# SENS.net
KiCad netlist of a schematic drawn in Altium Designer
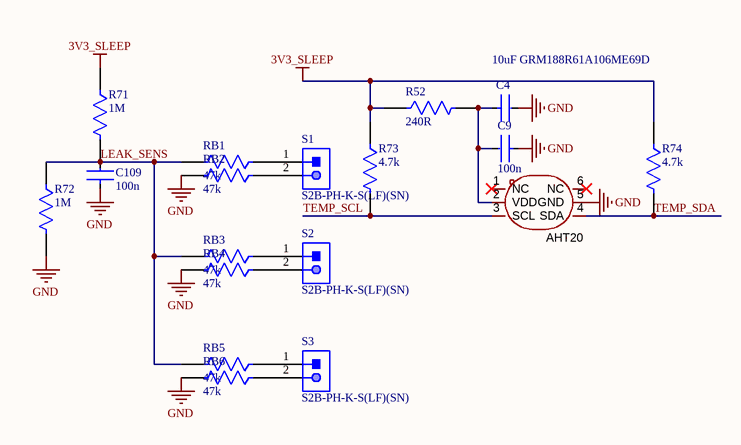
[diagram p0: SENS.SchDoc]

(export (version "E")
  (design (tool "Eeschema 10.0.6"))
  (components
    (comp (ref "C4")
      (value "10uF GRM188R61A106ME69D")
      (footprint "FP-GRM188-0_15-MFG")
      (description "C19702")
      (fields (field (name "TOLERANCE") "20%"))
      (libsource (lib "LEAKCAM") (part "CMP-06035-003612-1"))
    )
    (comp (ref "C9")
      (value "100n")
      (footprint "CAP_0402")
      (description "C307331")
      (fields (field (name "TOLERANCE") "10%"))
      (libsource (lib "LEAKCAM") (part "CMP-03422-001116-1"))
    )
    (comp (ref "C109")
      (value "100n")
      (footprint "CAP_0402")
      (description "C307331")
      (fields (field (name "TOLERANCE") "10%"))
      (libsource (lib "LEAKCAM") (part "CMP-03422-001116-1"))
    )
    (comp (ref "R52")
      (value "240R")
      (footprint "RES_0402")
      (description "C324768")
      (fields (field (name "TOLERANCE") "1%"))
      (libsource (lib "LEAKCAM") (part "CMP-03412-016018-1"))
    )
    (comp (ref "R71")
      (value "1M")
      (footprint "RES_0402")
      (description "C26083")
      (fields (field (name "TOLERANCE") "1%"))
      (libsource (lib "LEAKCAM") (part "CMP-03412-016018-1"))
    )
    (comp (ref "R72")
      (value "1M")
      (footprint "RES_0402")
      (description "C26083")
      (fields (field (name "TOLERANCE") "1%"))
      (libsource (lib "LEAKCAM") (part "CMP-03412-016018-1"))
    )
    (comp (ref "R73")
      (value "4.7k")
      (footprint "RES_0402")
      (description "C25900")
      (fields (field (name "TOLERANCE") "1%"))
      (libsource (lib "LEAKCAM") (part "CMP-03412-016018-1"))
    )
    (comp (ref "R74")
      (value "4.7k")
      (footprint "RES_0402")
      (description "C25900")
      (fields (field (name "TOLERANCE") "1%"))
      (libsource (lib "LEAKCAM") (part "CMP-03412-016018-1"))
    )
    (comp (ref "RB1")
      (value "47k")
      (footprint "RES_0402")
      (description "C25792")
      (fields (field (name "TOLERANCE") "1%"))
      (libsource (lib "LEAKCAM") (part "CMP-03412-016018-1"))
    )
    (comp (ref "RB2")
      (value "47k")
      (footprint "RES_0402")
      (description "C25792")
      (fields (field (name "TOLERANCE") "1%"))
      (libsource (lib "LEAKCAM") (part "CMP-03412-016018-1"))
    )
    (comp (ref "RB3")
      (value "47k")
      (footprint "RES_0402")
      (description "C25792")
      (fields (field (name "TOLERANCE") "1%"))
      (libsource (lib "LEAKCAM") (part "CMP-03412-016018-1"))
    )
    (comp (ref "RB4")
      (value "47k")
      (footprint "RES_0402")
      (description "C25792")
      (fields (field (name "TOLERANCE") "1%"))
      (libsource (lib "LEAKCAM") (part "CMP-03412-016018-1"))
    )
    (comp (ref "RB5")
      (value "47k")
      (footprint "RES_0402")
      (description "C25792")
      (fields (field (name "TOLERANCE") "1%"))
      (libsource (lib "LEAKCAM") (part "CMP-03412-016018-1"))
    )
    (comp (ref "RB6")
      (value "47k")
      (footprint "RES_0402")
      (description "C25792")
      (fields (field (name "TOLERANCE") "1%"))
      (libsource (lib "LEAKCAM") (part "CMP-03412-016018-1"))
    )
    (comp (ref "S1")
      (value "S2B-PH-K-S(LF)(SN)")
      (footprint "JST-S2B-PH-K-S_V")
      (description "C157932")
      (fields (field (name "TOLERANCE") "20%"))
      (libsource (lib "LEAKCAM") (part "CMP-1755-00004-1"))
    )
    (comp (ref "S2")
      (value "S2B-PH-K-S(LF)(SN)")
      (footprint "JST-S2B-PH-K-S_V")
      (description "C157932")
      (fields (field (name "TOLERANCE") "20%"))
      (libsource (lib "LEAKCAM") (part "CMP-1755-00004-1"))
    )
    (comp (ref "S3")
      (value "S2B-PH-K-S(LF)(SN)")
      (footprint "JST-S2B-PH-K-S_V")
      (description "C157932")
      (fields (field (name "TOLERANCE") "20%"))
      (libsource (lib "LEAKCAM") (part "CMP-1755-00004-1"))
    )
    (comp (ref "U17")
      (value "AHT20")
      (footprint "AHT30")
      (description "C2757850")
      (fields (field (name "MANUFACTURER") "广州奥松") (field (name "MANUFACTURERPART") "AHT30"))
      (libsource (lib "LEAKCAM") (part "aht30_c45354925"))
    )
  )
  (nets
    (net (code "1") (name "/LEAK_SENS") (class "Default")
      (node (ref "C109") (pin "2") (pinfunction "2_2") (pintype "passive"))
      (node (ref "R71") (pin "2") (pinfunction "2_2") (pintype "passive"))
      (node (ref "R72") (pin "1") (pinfunction "1_1") (pintype "passive"))
      (node (ref "RB1") (pin "2") (pinfunction "2_2") (pintype "passive"))
      (node (ref "RB3") (pin "2") (pinfunction "2_2") (pintype "passive"))
      (node (ref "RB5") (pin "2") (pinfunction "2_2") (pintype "passive"))
    )
    (net (code "2") (name "/TEMP_SCL") (class "Default")
      (node (ref "R73") (pin "2") (pinfunction "2_2") (pintype "passive"))
      (node (ref "U17") (pin "3") (pinfunction "SCL_3") (pintype "passive"))
    )
    (net (code "3") (name "/TEMP_SDA") (class "Default")
      (node (ref "R74") (pin "2") (pinfunction "2_2") (pintype "passive"))
      (node (ref "U17") (pin "4") (pinfunction "SDA_4") (pintype "passive"))
    )
    (net (code "4") (name "3V3_SLEEP") (class "Default")
      (node (ref "R52") (pin "1") (pinfunction "1_1") (pintype "passive"))
      (node (ref "R71") (pin "1") (pinfunction "1_1") (pintype "passive"))
      (node (ref "R73") (pin "1") (pinfunction "1_1") (pintype "passive"))
      (node (ref "R74") (pin "1") (pinfunction "1_1") (pintype "passive"))
    )
    (net (code "5") (name "GND") (class "Default")
      (node (ref "C109") (pin "1") (pinfunction "1_1") (pintype "passive"))
      (node (ref "C4") (pin "2") (pinfunction "2_2") (pintype "passive"))
      (node (ref "C9") (pin "1") (pinfunction "1_1") (pintype "passive"))
      (node (ref "R72") (pin "2") (pinfunction "2_2") (pintype "passive"))
      (node (ref "RB2") (pin "2") (pinfunction "2_2") (pintype "passive"))
      (node (ref "RB4") (pin "2") (pinfunction "2_2") (pintype "passive"))
      (node (ref "RB6") (pin "2") (pinfunction "2_2") (pintype "passive"))
      (node (ref "U17") (pin "5") (pinfunction "GND_5") (pintype "passive"))
    )
    (net (code "6") (name "Net-(RB1-Pad1)") (class "Default")
      (node (ref "RB1") (pin "1") (pinfunction "1_1") (pintype "passive"))
      (node (ref "S1") (pin "1") (pinfunction "1_1") (pintype "passive"))
    )
    (net (code "7") (name "Net-(RB2-Pad1)") (class "Default")
      (node (ref "RB2") (pin "1") (pinfunction "1_1") (pintype "passive"))
      (node (ref "S1") (pin "2") (pinfunction "2_2") (pintype "passive"))
    )
    (net (code "8") (name "Net-(RB3-Pad1)") (class "Default")
      (node (ref "RB3") (pin "1") (pinfunction "1_1") (pintype "passive"))
      (node (ref "S2") (pin "1") (pinfunction "1_1") (pintype "passive"))
    )
    (net (code "9") (name "Net-(RB4-Pad1)") (class "Default")
      (node (ref "RB4") (pin "1") (pinfunction "1_1") (pintype "passive"))
      (node (ref "S2") (pin "2") (pinfunction "2_2") (pintype "passive"))
    )
    (net (code "10") (name "Net-(RB5-Pad1)") (class "Default")
      (node (ref "RB5") (pin "1") (pinfunction "1_1") (pintype "passive"))
      (node (ref "S3") (pin "1") (pinfunction "1_1") (pintype "passive"))
    )
    (net (code "11") (name "Net-(RB6-Pad1)") (class "Default")
      (node (ref "RB6") (pin "1") (pinfunction "1_1") (pintype "passive"))
      (node (ref "S3") (pin "2") (pinfunction "2_2") (pintype "passive"))
    )
    (net (code "12") (name "Net-(U17-VDD)") (class "Default")
      (node (ref "C4") (pin "1") (pinfunction "1_1") (pintype "passive"))
      (node (ref "C9") (pin "2") (pinfunction "2_2") (pintype "passive"))
      (node (ref "R52") (pin "2") (pinfunction "2_2") (pintype "passive"))
      (node (ref "U17") (pin "2") (pinfunction "VDD_2") (pintype "passive"))
    )
    (net (code "13") (name "unconnected-(U17-NC-Pad1)") (class "Default")
      (node (ref "U17") (pin "1") (pinfunction "NC_1") (pintype "passive+no_connect"))
    )
    (net (code "14") (name "unconnected-(U17-NC-Pad6)") (class "Default")
      (node (ref "U17") (pin "6") (pinfunction "NC_6") (pintype "passive+no_connect"))
    )
  )
)
